# FPGA_POWER.net
KiCad netlist of a schematic drawn in Altium Designer
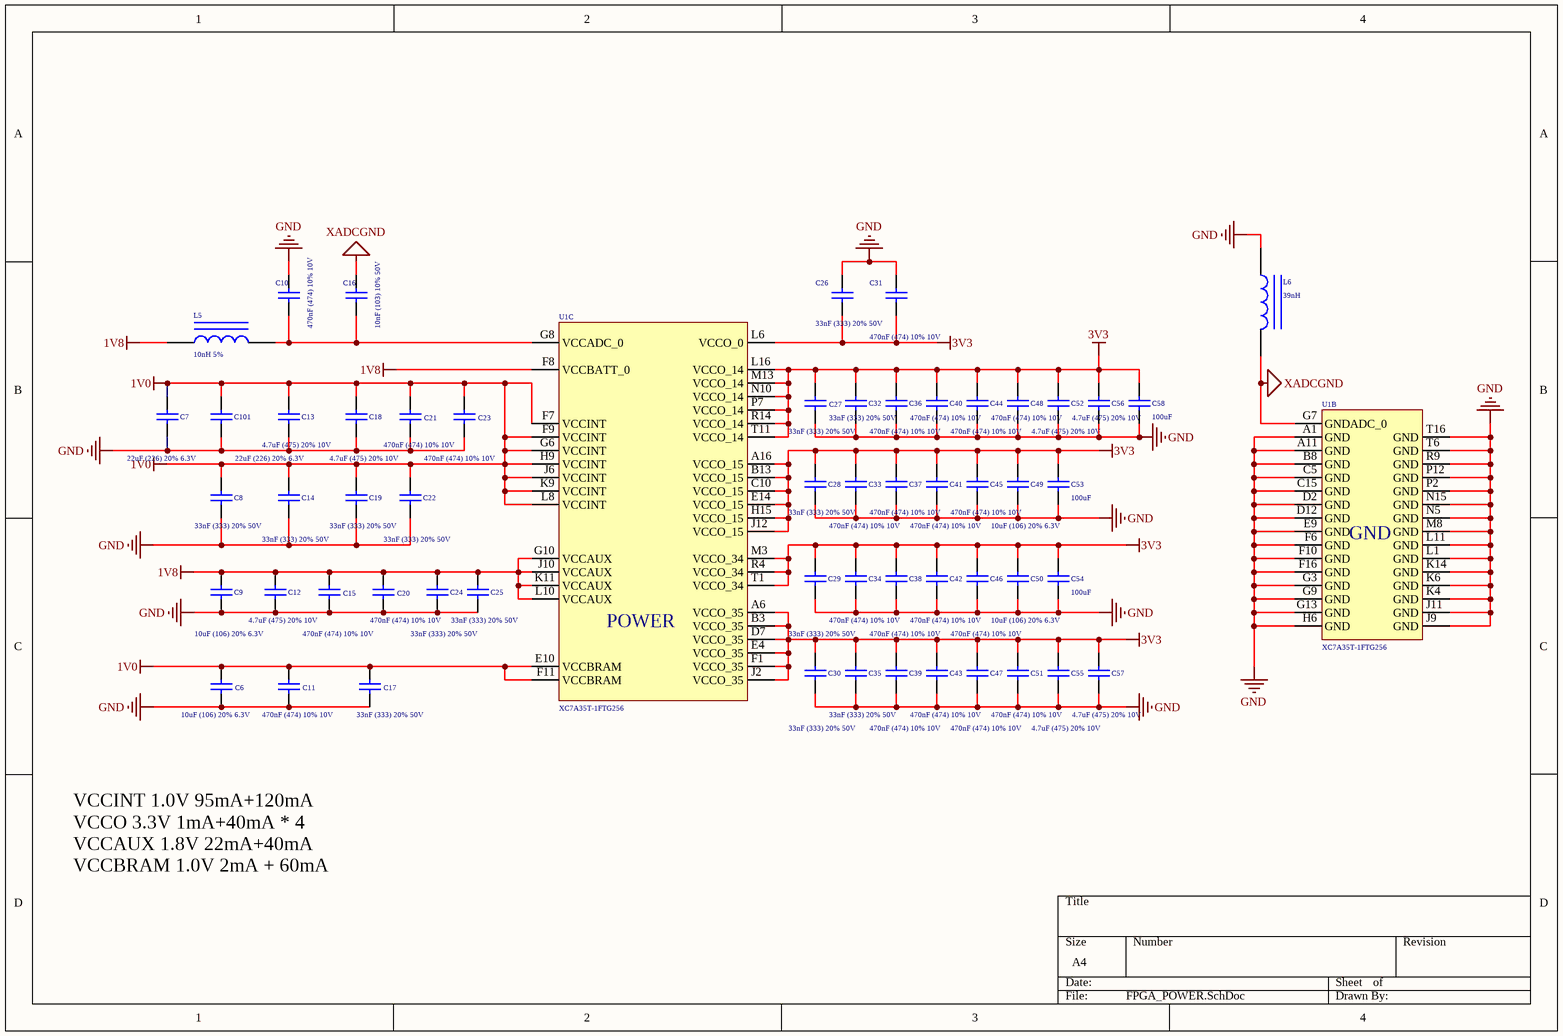
[diagram p0: FPGA_POWER.SchDoc]

(export (version "E")
  (design (tool "Eeschema 10.0.6"))
  (components
    (comp (ref "C6")
      (value "10uF (106) 20% 6.3V")
      (footprint "0402_C")
      (description "贴片电容")
      (libsource (lib "Cap") (part "0402 10uF (106) 20% 6.3V"))
    )
    (comp (ref "C7")
      (value "22uF (226) 20% 6.3V")
      (footprint "0603_C")
      (description "贴片电容")
      (libsource (lib "Miscellaneous Devices LC") (part "0603 22uF (226) 20% 6.3V"))
    )
    (comp (ref "C8")
      (value "33nF (333) 20% 50V")
      (footprint "0402_C")
      (description "贴片电容")
      (libsource (lib "Cap") (part "0402 33nF (333) 20% 50V"))
    )
    (comp (ref "C9")
      (value "10uF (106) 20% 6.3V")
      (footprint "0402_C")
      (description "贴片电容")
      (libsource (lib "Cap") (part "0402 10uF (106) 20% 6.3V"))
    )
    (comp (ref "C10")
      (value "470nF (474) 10% 10V")
      (footprint "0402_C")
      (description "贴片电容")
      (libsource (lib "Cap") (part "0402 470nF (474) 10% 10V"))
    )
    (comp (ref "C11")
      (value "470nF (474) 10% 10V")
      (footprint "0402_C")
      (description "贴片电容")
      (libsource (lib "Cap") (part "0402 470nF (474) 10% 10V"))
    )
    (comp (ref "C12")
      (value "4.7uF (475) 20% 10V")
      (footprint "0402_C")
      (description "贴片电容")
      (libsource (lib "Cap") (part "0402 4.7uF (475) 20% 10V"))
    )
    (comp (ref "C13")
      (value "4.7uF (475) 20% 10V")
      (footprint "0402_C")
      (description "贴片电容")
      (libsource (lib "Cap") (part "0402 4.7uF (475) 20% 10V"))
    )
    (comp (ref "C14")
      (value "33nF (333) 20% 50V")
      (footprint "0402_C")
      (description "贴片电容")
      (libsource (lib "Cap") (part "0402 33nF (333) 20% 50V"))
    )
    (comp (ref "C15")
      (value "470nF (474) 10% 10V")
      (footprint "0402_C")
      (description "贴片电容")
      (libsource (lib "Cap") (part "0402 470nF (474) 10% 10V"))
    )
    (comp (ref "C16")
      (value "10nF (103) 10% 50V")
      (footprint "0402_C")
      (description "贴片电容")
      (libsource (lib "Cap") (part "0402 10nF (103) 10% 50V"))
    )
    (comp (ref "C17")
      (value "33nF (333) 20% 50V")
      (footprint "0402_C")
      (description "贴片电容")
      (libsource (lib "Cap") (part "0402 33nF (333) 20% 50V"))
    )
    (comp (ref "C18")
      (value "4.7uF (475) 20% 10V")
      (footprint "0402_C")
      (description "贴片电容")
      (libsource (lib "Cap") (part "0402 4.7uF (475) 20% 10V"))
    )
    (comp (ref "C19")
      (value "33nF (333) 20% 50V")
      (footprint "0402_C")
      (description "贴片电容")
      (libsource (lib "Cap") (part "0402 33nF (333) 20% 50V"))
    )
    (comp (ref "C20")
      (value "470nF (474) 10% 10V")
      (footprint "0402_C")
      (description "贴片电容")
      (libsource (lib "Cap") (part "0402 470nF (474) 10% 10V"))
    )
    (comp (ref "C21")
      (value "470nF (474) 10% 10V")
      (footprint "0402_C")
      (description "贴片电容")
      (libsource (lib "Cap") (part "0402 470nF (474) 10% 10V"))
    )
    (comp (ref "C22")
      (value "33nF (333) 20% 50V")
      (footprint "0402_C")
      (description "贴片电容")
      (libsource (lib "Cap") (part "0402 33nF (333) 20% 50V"))
    )
    (comp (ref "C23")
      (value "470nF (474) 10% 10V")
      (footprint "0402_C")
      (description "贴片电容")
      (libsource (lib "Cap") (part "0402 470nF (474) 10% 10V"))
    )
    (comp (ref "C24")
      (value "33nF (333) 20% 50V")
      (footprint "0402_C")
      (description "贴片电容")
      (libsource (lib "Cap") (part "0402 33nF (333) 20% 50V"))
    )
    (comp (ref "C25")
      (value "33nF (333) 20% 50V")
      (footprint "0402_C")
      (description "贴片电容")
      (libsource (lib "Cap") (part "0402 33nF (333) 20% 50V"))
    )
    (comp (ref "C26")
      (value "33nF (333) 20% 50V")
      (footprint "0402_C")
      (description "贴片电容")
      (libsource (lib "Cap") (part "0402 33nF (333) 20% 50V"))
    )
    (comp (ref "C27")
      (value "33nF (333) 20% 50V")
      (footprint "0402_C")
      (description "贴片电容")
      (libsource (lib "Cap") (part "0402 33nF (333) 20% 50V"))
    )
    (comp (ref "C28")
      (value "33nF (333) 20% 50V")
      (footprint "0402_C")
      (description "贴片电容")
      (libsource (lib "Cap") (part "0402 33nF (333) 20% 50V"))
    )
    (comp (ref "C29")
      (value "33nF (333) 20% 50V")
      (footprint "0402_C")
      (description "贴片电容")
      (libsource (lib "Cap") (part "0402 33nF (333) 20% 50V"))
    )
    (comp (ref "C30")
      (value "33nF (333) 20% 50V")
      (footprint "0402_C")
      (description "贴片电容")
      (libsource (lib "Cap") (part "0402 33nF (333) 20% 50V"))
    )
    (comp (ref "C31")
      (value "470nF (474) 10% 10V")
      (footprint "0402_C")
      (description "贴片电容")
      (libsource (lib "Cap") (part "0402 470nF (474) 10% 10V"))
    )
    (comp (ref "C32")
      (value "33nF (333) 20% 50V")
      (footprint "0402_C")
      (description "贴片电容")
      (libsource (lib "Cap") (part "0402 33nF (333) 20% 50V"))
    )
    (comp (ref "C33")
      (value "470nF (474) 10% 10V")
      (footprint "0402_C")
      (description "贴片电容")
      (libsource (lib "Cap") (part "0402 470nF (474) 10% 10V"))
    )
    (comp (ref "C34")
      (value "470nF (474) 10% 10V")
      (footprint "0402_C")
      (description "贴片电容")
      (libsource (lib "Cap") (part "0402 470nF (474) 10% 10V"))
    )
    (comp (ref "C35")
      (value "33nF (333) 20% 50V")
      (footprint "0402_C")
      (description "贴片电容")
      (libsource (lib "Cap") (part "0402 33nF (333) 20% 50V"))
    )
    (comp (ref "C36")
      (value "470nF (474) 10% 10V")
      (footprint "0402_C")
      (description "贴片电容")
      (libsource (lib "Cap") (part "0402 470nF (474) 10% 10V"))
    )
    (comp (ref "C37")
      (value "470nF (474) 10% 10V")
      (footprint "0402_C")
      (description "贴片电容")
      (libsource (lib "Cap") (part "0402 470nF (474) 10% 10V"))
    )
    (comp (ref "C38")
      (value "470nF (474) 10% 10V")
      (footprint "0402_C")
      (description "贴片电容")
      (libsource (lib "Cap") (part "0402 470nF (474) 10% 10V"))
    )
    (comp (ref "C39")
      (value "470nF (474) 10% 10V")
      (footprint "0402_C")
      (description "贴片电容")
      (libsource (lib "Cap") (part "0402 470nF (474) 10% 10V"))
    )
    (comp (ref "C40")
      (value "470nF (474) 10% 10V")
      (footprint "0402_C")
      (description "贴片电容")
      (libsource (lib "Cap") (part "0402 470nF (474) 10% 10V"))
    )
    (comp (ref "C41")
      (value "470nF (474) 10% 10V")
      (footprint "0402_C")
      (description "贴片电容")
      (libsource (lib "Cap") (part "0402 470nF (474) 10% 10V"))
    )
    (comp (ref "C42")
      (value "470nF (474) 10% 10V")
      (footprint "0402_C")
      (description "贴片电容")
      (libsource (lib "Cap") (part "0402 470nF (474) 10% 10V"))
    )
    (comp (ref "C43")
      (value "470nF (474) 10% 10V")
      (footprint "0402_C")
      (description "贴片电容")
      (libsource (lib "Cap") (part "0402 470nF (474) 10% 10V"))
    )
    (comp (ref "C44")
      (value "470nF (474) 10% 10V")
      (footprint "0402_C")
      (description "贴片电容")
      (libsource (lib "Cap") (part "0402 470nF (474) 10% 10V"))
    )
    (comp (ref "C45")
      (value "470nF (474) 10% 10V")
      (footprint "0402_C")
      (description "贴片电容")
      (libsource (lib "Cap") (part "0402 470nF (474) 10% 10V"))
    )
    (comp (ref "C46")
      (value "470nF (474) 10% 10V")
      (footprint "0402_C")
      (description "贴片电容")
      (libsource (lib "Cap") (part "0402 470nF (474) 10% 10V"))
    )
    (comp (ref "C47")
      (value "470nF (474) 10% 10V")
      (footprint "0402_C")
      (description "贴片电容")
      (libsource (lib "Cap") (part "0402 470nF (474) 10% 10V"))
    )
    (comp (ref "C48")
      (value "470nF (474) 10% 10V")
      (footprint "0402_C")
      (description "贴片电容")
      (libsource (lib "Cap") (part "0402 470nF (474) 10% 10V"))
    )
    (comp (ref "C49")
      (value "10uF (106) 20% 6.3V")
      (footprint "0402_C")
      (description "贴片电容")
      (libsource (lib "Cap") (part "0402 10uF (106) 20% 6.3V"))
    )
    (comp (ref "C50")
      (value "10uF (106) 20% 6.3V")
      (footprint "0402_C")
      (description "贴片电容")
      (libsource (lib "Cap") (part "0402 10uF (106) 20% 6.3V"))
    )
    (comp (ref "C51")
      (value "470nF (474) 10% 10V")
      (footprint "0402_C")
      (description "贴片电容")
      (libsource (lib "Cap") (part "0402 470nF (474) 10% 10V"))
    )
    (comp (ref "C52")
      (value "4.7uF (475) 20% 10V")
      (footprint "0402_C")
      (description "贴片电容")
      (libsource (lib "Cap") (part "0402 4.7uF (475) 20% 10V"))
    )
    (comp (ref "C53")
      (value "100uF")
      (footprint "LC-1206")
      (description "贴片电容")
      (fields (field (name "Comment") "Cap") (field (name "PUBLISHER") "Altium Limited"))
      (libsource (lib "Sparks") (part "Cap"))
    )
    (comp (ref "C54")
      (value "100uF")
      (footprint "LC-1206")
      (description "贴片电容")
      (fields (field (name "Comment") "Cap") (field (name "PUBLISHER") "Altium Limited"))
      (libsource (lib "Sparks") (part "Cap"))
    )
    (comp (ref "C55")
      (value "4.7uF (475) 20% 10V")
      (footprint "0402_C")
      (description "贴片电容")
      (libsource (lib "Cap") (part "0402 4.7uF (475) 20% 10V"))
    )
    (comp (ref "C56")
      (value "4.7uF (475) 20% 10V")
      (footprint "0402_C")
      (description "贴片电容")
      (libsource (lib "Cap") (part "0402 4.7uF (475) 20% 10V"))
    )
    (comp (ref "C57")
      (value "4.7uF (475) 20% 10V")
      (footprint "0402_C")
      (description "贴片电容")
      (libsource (lib "Cap") (part "0402 4.7uF (475) 20% 10V"))
    )
    (comp (ref "C58")
      (value "100uF")
      (footprint "LC-1206")
      (description "贴片电容")
      (fields (field (name "Comment") "Cap") (field (name "PUBLISHER") "Altium Limited"))
      (libsource (lib "Sparks") (part "Cap"))
    )
    (comp (ref "C101")
      (value "22uF (226) 20% 6.3V")
      (footprint "0603_C")
      (description "贴片电容")
      (libsource (lib "Miscellaneous Devices LC") (part "0603 22uF (226) 20% 6.3V"))
    )
    (comp (ref "L5")
      (value "10nH 5%")
      (footprint "0402_L")
      (description "贴片电感")
      (libsource (lib "IUD") (part "0402 10nH 5%"))
    )
    (comp (ref "L6")
      (value "39nH")
      (footprint "0402_L")
      (description "贴片电感")
      (libsource (lib "IUD") (part "0402 39nH"))
    )
    (comp (ref "U1")
      (value "XC7A35T-1FTG256")
      (footprint "BGA100P9X9-81A")
      (libsource (lib "Schlib") (part "XC7A35T-1FTG256"))
    )
  )
  (nets
    (net (code "1") (name "1V0") (class "Default")
      (node (ref "C101") (pin "2") (pinfunction "2_2") (pintype "passive"))
      (node (ref "C11") (pin "2") (pinfunction "2_2") (pintype "passive"))
      (node (ref "C13") (pin "2") (pinfunction "2_2") (pintype "passive"))
      (node (ref "C14") (pin "2") (pinfunction "2_2") (pintype "passive"))
      (node (ref "C17") (pin "2") (pinfunction "2_2") (pintype "passive"))
      (node (ref "C18") (pin "2") (pinfunction "2_2") (pintype "passive"))
      (node (ref "C19") (pin "2") (pinfunction "2_2") (pintype "passive"))
      (node (ref "C21") (pin "2") (pinfunction "2_2") (pintype "passive"))
      (node (ref "C22") (pin "2") (pinfunction "2_2") (pintype "passive"))
      (node (ref "C23") (pin "2") (pinfunction "2_2") (pintype "passive"))
      (node (ref "C6") (pin "2") (pinfunction "2_2") (pintype "passive"))
      (node (ref "C7") (pin "2") (pinfunction "2_2") (pintype "passive"))
      (node (ref "C8") (pin "2") (pinfunction "2_2") (pintype "passive"))
      (node (ref "U1") (pin "E10") (pinfunction "VCCBRAM_E10") (pintype "passive"))
      (node (ref "U1") (pin "F11") (pinfunction "VCCBRAM_F11") (pintype "passive"))
      (node (ref "U1") (pin "F7") (pinfunction "VCCINT_F7") (pintype "passive"))
      (node (ref "U1") (pin "F9") (pinfunction "VCCINT_F9") (pintype "passive"))
      (node (ref "U1") (pin "G6") (pinfunction "VCCINT_G6") (pintype "passive"))
      (node (ref "U1") (pin "H9") (pinfunction "VCCINT_H9") (pintype "passive"))
      (node (ref "U1") (pin "J6") (pinfunction "VCCINT_J6") (pintype "passive"))
      (node (ref "U1") (pin "K9") (pinfunction "VCCINT_K9") (pintype "passive"))
      (node (ref "U1") (pin "L8") (pinfunction "VCCINT_L8") (pintype "passive"))
    )
    (net (code "2") (name "1V8") (class "Default")
      (node (ref "C12") (pin "2") (pinfunction "2_2") (pintype "passive"))
      (node (ref "C15") (pin "2") (pinfunction "2_2") (pintype "passive"))
      (node (ref "C20") (pin "2") (pinfunction "2_2") (pintype "passive"))
      (node (ref "C24") (pin "2") (pinfunction "2_2") (pintype "passive"))
      (node (ref "C25") (pin "2") (pinfunction "2_2") (pintype "passive"))
      (node (ref "C9") (pin "2") (pinfunction "2_2") (pintype "passive"))
      (node (ref "L5") (pin "1") (pinfunction "1_1") (pintype "passive"))
      (node (ref "U1") (pin "F8") (pinfunction "VCCBATT_0_F8") (pintype "passive"))
      (node (ref "U1") (pin "G10") (pinfunction "VCCAUX_G10") (pintype "passive"))
      (node (ref "U1") (pin "J10") (pinfunction "VCCAUX_J10") (pintype "passive"))
      (node (ref "U1") (pin "K11") (pinfunction "VCCAUX_K11") (pintype "passive"))
      (node (ref "U1") (pin "L10") (pinfunction "VCCAUX_L10") (pintype "passive"))
    )
    (net (code "3") (name "3V3") (class "Default")
      (node (ref "C26") (pin "1") (pinfunction "1_1") (pintype "passive"))
      (node (ref "C27") (pin "2") (pinfunction "2_2") (pintype "passive"))
      (node (ref "C28") (pin "2") (pinfunction "2_2") (pintype "passive"))
      (node (ref "C29") (pin "2") (pinfunction "2_2") (pintype "passive"))
      (node (ref "C30") (pin "2") (pinfunction "2_2") (pintype "passive"))
      (node (ref "C31") (pin "1") (pinfunction "1_1") (pintype "passive"))
      (node (ref "C32") (pin "2") (pinfunction "2_2") (pintype "passive"))
      (node (ref "C33") (pin "2") (pinfunction "2_2") (pintype "passive"))
      (node (ref "C34") (pin "2") (pinfunction "2_2") (pintype "passive"))
      (node (ref "C35") (pin "2") (pinfunction "2_2") (pintype "passive"))
      (node (ref "C36") (pin "2") (pinfunction "2_2") (pintype "passive"))
      (node (ref "C37") (pin "2") (pinfunction "2_2") (pintype "passive"))
      (node (ref "C38") (pin "2") (pinfunction "2_2") (pintype "passive"))
      (node (ref "C39") (pin "2") (pinfunction "2_2") (pintype "passive"))
      (node (ref "C40") (pin "2") (pinfunction "2_2") (pintype "passive"))
      (node (ref "C41") (pin "2") (pinfunction "2_2") (pintype "passive"))
      (node (ref "C42") (pin "2") (pinfunction "2_2") (pintype "passive"))
      (node (ref "C43") (pin "2") (pinfunction "2_2") (pintype "passive"))
      (node (ref "C44") (pin "2") (pinfunction "2_2") (pintype "passive"))
      (node (ref "C45") (pin "2") (pinfunction "2_2") (pintype "passive"))
      (node (ref "C46") (pin "2") (pinfunction "2_2") (pintype "passive"))
      (node (ref "C47") (pin "2") (pinfunction "2_2") (pintype "passive"))
      (node (ref "C48") (pin "2") (pinfunction "2_2") (pintype "passive"))
      (node (ref "C49") (pin "2") (pinfunction "2_2") (pintype "passive"))
      (node (ref "C50") (pin "2") (pinfunction "2_2") (pintype "passive"))
      (node (ref "C51") (pin "2") (pinfunction "2_2") (pintype "passive"))
      (node (ref "C52") (pin "2") (pinfunction "2_2") (pintype "passive"))
      (node (ref "C53") (pin "2") (pinfunction "2_2") (pintype "passive"))
      (node (ref "C54") (pin "2") (pinfunction "2_2") (pintype "passive"))
      (node (ref "C55") (pin "2") (pinfunction "2_2") (pintype "passive"))
      (node (ref "C56") (pin "2") (pinfunction "2_2") (pintype "passive"))
      (node (ref "C57") (pin "2") (pinfunction "2_2") (pintype "passive"))
      (node (ref "C58") (pin "2") (pinfunction "2_2") (pintype "passive"))
      (node (ref "U1") (pin "A16") (pinfunction "VCCO_15_A16") (pintype "passive"))
      (node (ref "U1") (pin "A6") (pinfunction "VCCO_35_A6") (pintype "passive"))
      (node (ref "U1") (pin "B13") (pinfunction "VCCO_15_B13") (pintype "passive"))
      (node (ref "U1") (pin "B3") (pinfunction "VCCO_35_B3") (pintype "passive"))
      (node (ref "U1") (pin "C10") (pinfunction "VCCO_15_C10") (pintype "passive"))
      (node (ref "U1") (pin "D7") (pinfunction "VCCO_35_D7") (pintype "passive"))
      (node (ref "U1") (pin "E14") (pinfunction "VCCO_15_E14") (pintype "passive"))
      (node (ref "U1") (pin "E4") (pinfunction "VCCO_35_E4") (pintype "passive"))
      (node (ref "U1") (pin "F1") (pinfunction "VCCO_35_F1") (pintype "passive"))
      (node (ref "U1") (pin "H15") (pinfunction "VCCO_15_H15") (pintype "passive"))
      (node (ref "U1") (pin "J12") (pinfunction "VCCO_15_J12") (pintype "passive"))
      (node (ref "U1") (pin "J2") (pinfunction "VCCO_35_J2") (pintype "passive"))
      (node (ref "U1") (pin "L16") (pinfunction "VCCO_14_L16") (pintype "passive"))
      (node (ref "U1") (pin "L6") (pinfunction "VCCO_0_L6") (pintype "passive"))
      (node (ref "U1") (pin "M13") (pinfunction "VCCO_14_M13") (pintype "passive"))
      (node (ref "U1") (pin "M3") (pinfunction "VCCO_34_M3") (pintype "passive"))
      (node (ref "U1") (pin "N10") (pinfunction "VCCO_14_N10") (pintype "passive"))
      (node (ref "U1") (pin "P7") (pinfunction "VCCO_14_P7") (pintype "passive"))
      (node (ref "U1") (pin "R14") (pinfunction "VCCO_14_R14") (pintype "passive"))
      (node (ref "U1") (pin "R4") (pinfunction "VCCO_34_R4") (pintype "passive"))
      (node (ref "U1") (pin "T1") (pinfunction "VCCO_34_T1") (pintype "passive"))
      (node (ref "U1") (pin "T11") (pinfunction "VCCO_14_T11") (pintype "passive"))
    )
    (net (code "4") (name "GND") (class "Default")
      (node (ref "C10") (pin "2") (pinfunction "2_2") (pintype "passive"))
      (node (ref "C101") (pin "1") (pinfunction "1_1") (pintype "passive"))
      (node (ref "C11") (pin "1") (pinfunction "1_1") (pintype "passive"))
      (node (ref "C12") (pin "1") (pinfunction "1_1") (pintype "passive"))
      (node (ref "C13") (pin "1") (pinfunction "1_1") (pintype "passive"))
      (node (ref "C14") (pin "1") (pinfunction "1_1") (pintype "passive"))
      (node (ref "C15") (pin "1") (pinfunction "1_1") (pintype "passive"))
      (node (ref "C17") (pin "1") (pinfunction "1_1") (pintype "passive"))
      (node (ref "C18") (pin "1") (pinfunction "1_1") (pintype "passive"))
      (node (ref "C19") (pin "1") (pinfunction "1_1") (pintype "passive"))
      (node (ref "C20") (pin "1") (pinfunction "1_1") (pintype "passive"))
      (node (ref "C21") (pin "1") (pinfunction "1_1") (pintype "passive"))
      (node (ref "C22") (pin "1") (pinfunction "1_1") (pintype "passive"))
      (node (ref "C23") (pin "1") (pinfunction "1_1") (pintype "passive"))
      (node (ref "C24") (pin "1") (pinfunction "1_1") (pintype "passive"))
      (node (ref "C25") (pin "1") (pinfunction "1_1") (pintype "passive"))
      (node (ref "C26") (pin "2") (pinfunction "2_2") (pintype "passive"))
      (node (ref "C27") (pin "1") (pinfunction "1_1") (pintype "passive"))
      (node (ref "C28") (pin "1") (pinfunction "1_1") (pintype "passive"))
      (node (ref "C29") (pin "1") (pinfunction "1_1") (pintype "passive"))
      (node (ref "C30") (pin "1") (pinfunction "1_1") (pintype "passive"))
      (node (ref "C31") (pin "2") (pinfunction "2_2") (pintype "passive"))
      (node (ref "C32") (pin "1") (pinfunction "1_1") (pintype "passive"))
      (node (ref "C33") (pin "1") (pinfunction "1_1") (pintype "passive"))
      (node (ref "C34") (pin "1") (pinfunction "1_1") (pintype "passive"))
      (node (ref "C35") (pin "1") (pinfunction "1_1") (pintype "passive"))
      (node (ref "C36") (pin "1") (pinfunction "1_1") (pintype "passive"))
      (node (ref "C37") (pin "1") (pinfunction "1_1") (pintype "passive"))
      (node (ref "C38") (pin "1") (pinfunction "1_1") (pintype "passive"))
      (node (ref "C39") (pin "1") (pinfunction "1_1") (pintype "passive"))
      (node (ref "C40") (pin "1") (pinfunction "1_1") (pintype "passive"))
      (node (ref "C41") (pin "1") (pinfunction "1_1") (pintype "passive"))
      (node (ref "C42") (pin "1") (pinfunction "1_1") (pintype "passive"))
      (node (ref "C43") (pin "1") (pinfunction "1_1") (pintype "passive"))
      (node (ref "C44") (pin "1") (pinfunction "1_1") (pintype "passive"))
      (node (ref "C45") (pin "1") (pinfunction "1_1") (pintype "passive"))
      (node (ref "C46") (pin "1") (pinfunction "1_1") (pintype "passive"))
      (node (ref "C47") (pin "1") (pinfunction "1_1") (pintype "passive"))
      (node (ref "C48") (pin "1") (pinfunction "1_1") (pintype "passive"))
      (node (ref "C49") (pin "1") (pinfunction "1_1") (pintype "passive"))
      (node (ref "C50") (pin "1") (pinfunction "1_1") (pintype "passive"))
      (node (ref "C51") (pin "1") (pinfunction "1_1") (pintype "passive"))
      (node (ref "C52") (pin "1") (pinfunction "1_1") (pintype "passive"))
      (node (ref "C53") (pin "1") (pinfunction "1_1") (pintype "passive"))
      (node (ref "C54") (pin "1") (pinfunction "1_1") (pintype "passive"))
      (node (ref "C55") (pin "1") (pinfunction "1_1") (pintype "passive"))
      (node (ref "C56") (pin "1") (pinfunction "1_1") (pintype "passive"))
      (node (ref "C57") (pin "1") (pinfunction "1_1") (pintype "passive"))
      (node (ref "C58") (pin "1") (pinfunction "1_1") (pintype "passive"))
      (node (ref "C6") (pin "1") (pinfunction "1_1") (pintype "passive"))
      (node (ref "C7") (pin "1") (pinfunction "1_1") (pintype "passive"))
      (node (ref "C8") (pin "1") (pinfunction "1_1") (pintype "passive"))
      (node (ref "C9") (pin "1") (pinfunction "1_1") (pintype "passive"))
      (node (ref "L6") (pin "1") (pinfunction "1_1") (pintype "passive"))
      (node (ref "U1") (pin "A1") (pinfunction "GND_A1") (pintype "passive"))
      (node (ref "U1") (pin "A11") (pinfunction "GND_A11") (pintype "passive"))
      (node (ref "U1") (pin "B8") (pinfunction "GND_B8") (pintype "passive"))
      (node (ref "U1") (pin "C15") (pinfunction "GND_C15") (pintype "passive"))
      (node (ref "U1") (pin "C5") (pinfunction "GND_C5") (pintype "passive"))
      (node (ref "U1") (pin "D12") (pinfunction "GND_D12") (pintype "passive"))
      (node (ref "U1") (pin "D2") (pinfunction "GND_D2") (pintype "passive"))
      (node (ref "U1") (pin "E9") (pinfunction "GND_E9") (pintype "passive"))
      (node (ref "U1") (pin "F10") (pinfunction "GND_F10") (pintype "passive"))
      (node (ref "U1") (pin "F16") (pinfunction "GND_F16") (pintype "passive"))
      (node (ref "U1") (pin "F6") (pinfunction "GND_F6") (pintype "passive"))
      (node (ref "U1") (pin "G13") (pinfunction "GND_G13") (pintype "passive"))
      (node (ref "U1") (pin "G3") (pinfunction "GND_G3") (pintype "passive"))
      (node (ref "U1") (pin "G9") (pinfunction "GND_G9") (pintype "passive"))
      (node (ref "U1") (pin "H6") (pinfunction "GND_H6") (pintype "passive"))
      (node (ref "U1") (pin "J11") (pinfunction "GND_J11") (pintype "passive"))
      (node (ref "U1") (pin "J9") (pinfunction "GND_J9") (pintype "passive"))
      (node (ref "U1") (pin "K14") (pinfunction "GND_K14") (pintype "passive"))
      (node (ref "U1") (pin "K4") (pinfunction "GND_K4") (pintype "passive"))
      (node (ref "U1") (pin "K6") (pinfunction "GND_K6") (pintype "passive"))
      (node (ref "U1") (pin "L1") (pinfunction "GND_L1") (pintype "passive"))
      (node (ref "U1") (pin "L11") (pinfunction "GND_L11") (pintype "passive"))
      (node (ref "U1") (pin "M8") (pinfunction "GND_M8") (pintype "passive"))
      (node (ref "U1") (pin "N15") (pinfunction "GND_N15") (pintype "passive"))
      (node (ref "U1") (pin "N5") (pinfunction "GND_N5") (pintype "passive"))
      (node (ref "U1") (pin "P12") (pinfunction "GND_P12") (pintype "passive"))
      (node (ref "U1") (pin "P2") (pinfunction "GND_P2") (pintype "passive"))
      (node (ref "U1") (pin "R9") (pinfunction "GND_R9") (pintype "passive"))
      (node (ref "U1") (pin "T16") (pinfunction "GND_T16") (pintype "passive"))
      (node (ref "U1") (pin "T6") (pinfunction "GND_T6") (pintype "passive"))
    )
    (net (code "5") (name "Net-(U1C-VCCADC_0)") (class "Default")
      (node (ref "C10") (pin "1") (pinfunction "1_1") (pintype "passive"))
      (node (ref "C16") (pin "1") (pinfunction "1_1") (pintype "passive"))
      (node (ref "L5") (pin "2") (pinfunction "2_2") (pintype "passive"))
      (node (ref "U1") (pin "G8") (pinfunction "VCCADC_0_G8") (pintype "passive"))
    )
    (net (code "6") (name "XADCGND") (class "Default")
      (node (ref "C16") (pin "2") (pinfunction "2_2") (pintype "passive"))
      (node (ref "L6") (pin "2") (pinfunction "2_2") (pintype "passive"))
      (node (ref "U1") (pin "G7") (pinfunction "GNDADC_0_G7") (pintype "passive"))
    )
  )
)
